# Buzzer_LED.net
KiCad netlist of a schematic drawn in Altium Designer
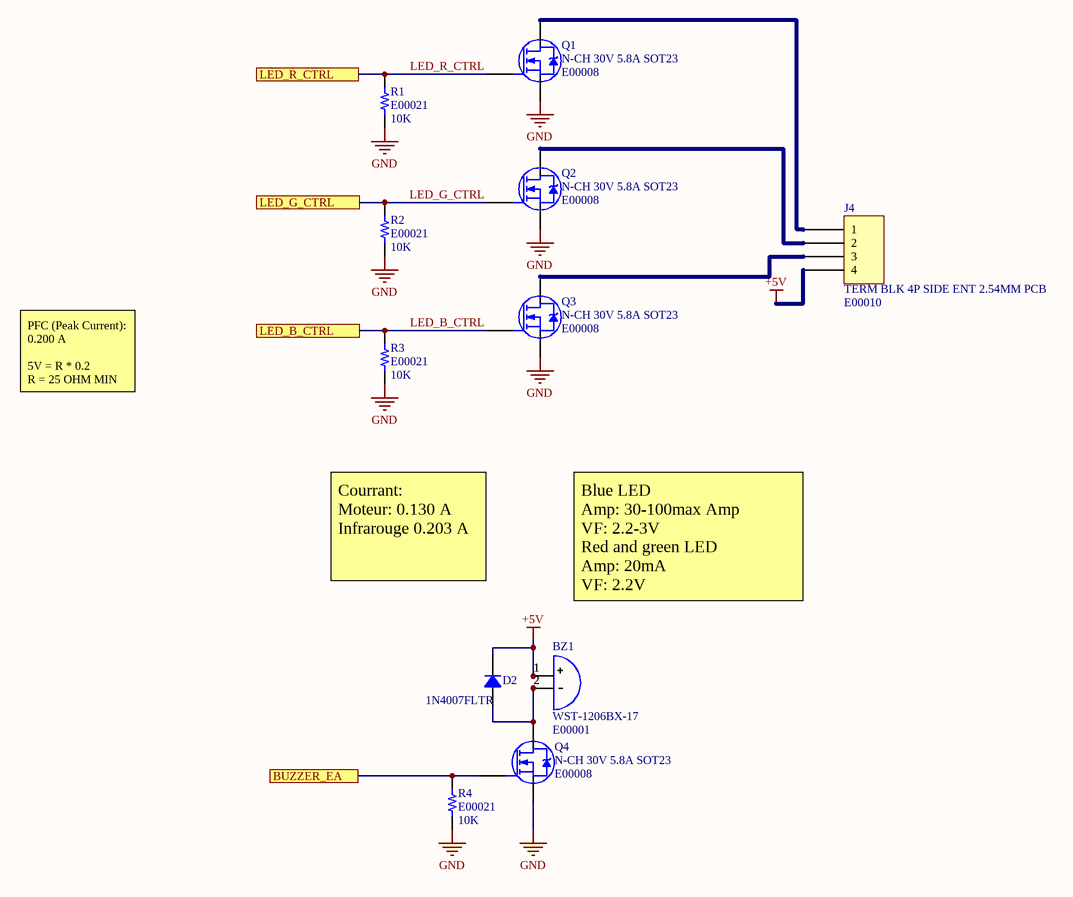
[diagram p0: Buzzer, LED.SchDoc]

(export (version "E")
  (design (tool "Eeschema 10.0.6"))
  (components
    (comp (ref "BZ1")
      (value "WST-1206BX-17")
      (footprint "BUZZ WST-1206BX")
      (description "Buzzers Indicator, Internally Driven Magnetic 5 V 30mA 3.1kHz 83dB @ 5V, 10cm Through Hole PC Pins")
      (fields (field (name "ADAM INVENTORY NUMBER 1") "E00001"))
      (libsource (lib "ADAM LIBRARY") (part "WST-1206BX-17"))
    )
    (comp (ref "D2")
      (value "1N4007FLTR")
      (footprint "SOD123F")
      (description "STANDARD RECTIFIER 1000V SOD-123")
      (fields (field (name "MANUFACTURER") "SMC Diode Solutions"))
      (libsource (lib "ADAM LIBRARY") (part "1N4007FLTR"))
    )
    (comp (ref "J4")
      (value "TERM BLK 4P SIDE ENT 2.54MM PCB")
      (footprint "TERM BLOC 4P")
      (fields
        (field (name "MANUFACTURER") "TE Connectivity AMP Connectors")
        (field (name "VOLTAGE") "150V")
        (field (name "ADAM INVENTORY NUMBER 1") "E00010")
      )
      (libsource (lib "ADAM LIBRARY") (part "TERM BLK 4P SIDE ENT 2.54MM PCB"))
    )
    (comp (ref "Q1")
      (value "N-CH 30V 5.8A SOT23")
      (footprint "N-CHANNEL TRANS")
      (description "N-Channel 5.8A (Tj) 350mW Surface Mount SOT-23")
      (fields (field (name "MANUFACTURER") "MCC") (field (name "ADAM INVENTORY NUMBER 1") "E00008"))
      (libsource (lib "ADAM LIBRARY") (part "TRANS N-CHANNEL 30V 5.8A SOT23"))
    )
    (comp (ref "Q2")
      (value "N-CH 30V 5.8A SOT23")
      (footprint "N-CHANNEL TRANS")
      (description "N-Channel 5.8A (Tj) 350mW Surface Mount SOT-23")
      (fields (field (name "MANUFACTURER") "MCC") (field (name "ADAM INVENTORY NUMBER 1") "E00008"))
      (libsource (lib "ADAM LIBRARY") (part "TRANS N-CHANNEL 30V 5.8A SOT23"))
    )
    (comp (ref "Q3")
      (value "N-CH 30V 5.8A SOT23")
      (footprint "N-CHANNEL TRANS")
      (description "N-Channel 5.8A (Tj) 350mW Surface Mount SOT-23")
      (fields (field (name "MANUFACTURER") "MCC") (field (name "ADAM INVENTORY NUMBER 1") "E00008"))
      (libsource (lib "ADAM LIBRARY") (part "TRANS N-CHANNEL 30V 5.8A SOT23"))
    )
    (comp (ref "Q4")
      (value "N-CH 30V 5.8A SOT23")
      (footprint "N-CHANNEL TRANS")
      (description "N-Channel 5.8A (Tj) 350mW Surface Mount SOT-23")
      (fields (field (name "MANUFACTURER") "MCC") (field (name "ADAM INVENTORY NUMBER 1") "E00008"))
      (libsource (lib "ADAM LIBRARY") (part "TRANS N-CHANNEL 30V 5.8A SOT23"))
    )
    (comp (ref "R1")
      (value "10K")
      (footprint "RES 0603")
      (description "RES SMD 10K OHM 1% 1/10W 0603")
      (fields
        (field (name "MANUFACTURER") "Rohm Semiconductor")
        (field (name "TOLERANCE") "±1%")
        (field (name "ADAM INVENTORY NUMBER 1") "E00021")
      )
      (libsource (lib "ADAM LIBRARY") (part "RES SMD 10K OHM"))
    )
    (comp (ref "R2")
      (value "10K")
      (footprint "RES 0603")
      (description "RES SMD 10K OHM 1% 1/10W 0603")
      (fields
        (field (name "MANUFACTURER") "Rohm Semiconductor")
        (field (name "TOLERANCE") "±1%")
        (field (name "ADAM INVENTORY NUMBER 1") "E00021")
      )
      (libsource (lib "ADAM LIBRARY") (part "RES SMD 10K OHM"))
    )
    (comp (ref "R3")
      (value "10K")
      (footprint "RES 0603")
      (description "RES SMD 10K OHM 1% 1/10W 0603")
      (fields
        (field (name "MANUFACTURER") "Rohm Semiconductor")
        (field (name "TOLERANCE") "±1%")
        (field (name "ADAM INVENTORY NUMBER 1") "E00021")
      )
      (libsource (lib "ADAM LIBRARY") (part "RES SMD 10K OHM"))
    )
    (comp (ref "R4")
      (value "10K")
      (footprint "RES 0603")
      (description "RES SMD 10K OHM 1% 1/10W 0603")
      (fields
        (field (name "MANUFACTURER") "Rohm Semiconductor")
        (field (name "TOLERANCE") "±1%")
        (field (name "ADAM INVENTORY NUMBER 1") "E00021")
      )
      (libsource (lib "ADAM LIBRARY") (part "RES SMD 10K OHM"))
    )
  )
  (nets
    (net (code "1") (name "+5V") (class "Default")
      (node (ref "BZ1") (pin "1") (pinfunction "1_1") (pintype "passive"))
      (node (ref "D2") (pin "2") (pinfunction "2_2") (pintype "passive"))
      (node (ref "J4") (pin "4") (pinfunction "4_4") (pintype "passive"))
    )
    (net (code "2") (name "/BUZZER_EA") (class "Default")
      (node (ref "Q4") (pin "1") (pinfunction "G_1") (pintype "passive"))
      (node (ref "R4") (pin "2") (pinfunction "2_2") (pintype "passive"))
    )
    (net (code "3") (name "/LED_B_CTRL") (class "Default")
      (node (ref "Q3") (pin "1") (pinfunction "G_1") (pintype "passive"))
      (node (ref "R3") (pin "2") (pinfunction "2_2") (pintype "passive"))
    )
    (net (code "4") (name "/LED_G_CTRL") (class "Default")
      (node (ref "Q2") (pin "1") (pinfunction "G_1") (pintype "passive"))
      (node (ref "R2") (pin "2") (pinfunction "2_2") (pintype "passive"))
    )
    (net (code "5") (name "/LED_R_CTRL") (class "Default")
      (node (ref "Q1") (pin "1") (pinfunction "G_1") (pintype "passive"))
      (node (ref "R1") (pin "2") (pinfunction "2_2") (pintype "passive"))
    )
    (net (code "6") (name "GND") (class "Default")
      (node (ref "Q1") (pin "2") (pinfunction "S_2") (pintype "passive"))
      (node (ref "Q2") (pin "2") (pinfunction "S_2") (pintype "passive"))
      (node (ref "Q3") (pin "2") (pinfunction "S_2") (pintype "passive"))
      (node (ref "Q4") (pin "2") (pinfunction "S_2") (pintype "passive"))
      (node (ref "R1") (pin "1") (pinfunction "1_1") (pintype "passive"))
      (node (ref "R2") (pin "1") (pinfunction "1_1") (pintype "passive"))
      (node (ref "R3") (pin "1") (pinfunction "1_1") (pintype "passive"))
      (node (ref "R4") (pin "1") (pinfunction "1_1") (pintype "passive"))
    )
    (net (code "7") (name "Net-(Q1-D)") (class "Default")
      (node (ref "J4") (pin "1") (pinfunction "1_1") (pintype "passive"))
      (node (ref "Q1") (pin "3") (pinfunction "D_3") (pintype "passive"))
    )
    (net (code "8") (name "Net-(Q2-D)") (class "Default")
      (node (ref "J4") (pin "2") (pinfunction "2_2") (pintype "passive"))
      (node (ref "Q2") (pin "3") (pinfunction "D_3") (pintype "passive"))
    )
    (net (code "9") (name "Net-(Q3-D)") (class "Default")
      (node (ref "J4") (pin "3") (pinfunction "3_3") (pintype "passive"))
      (node (ref "Q3") (pin "3") (pinfunction "D_3") (pintype "passive"))
    )
    (net (code "10") (name "Net-(Q4-D)") (class "Default")
      (node (ref "BZ1") (pin "2") (pinfunction "2_2") (pintype "passive"))
      (node (ref "D2") (pin "1") (pinfunction "1_1") (pintype "passive"))
      (node (ref "Q4") (pin "3") (pinfunction "D_3") (pintype "passive"))
    )
  )
)
